# USB-C.net
KiCad netlist of a schematic drawn in Altium Designer
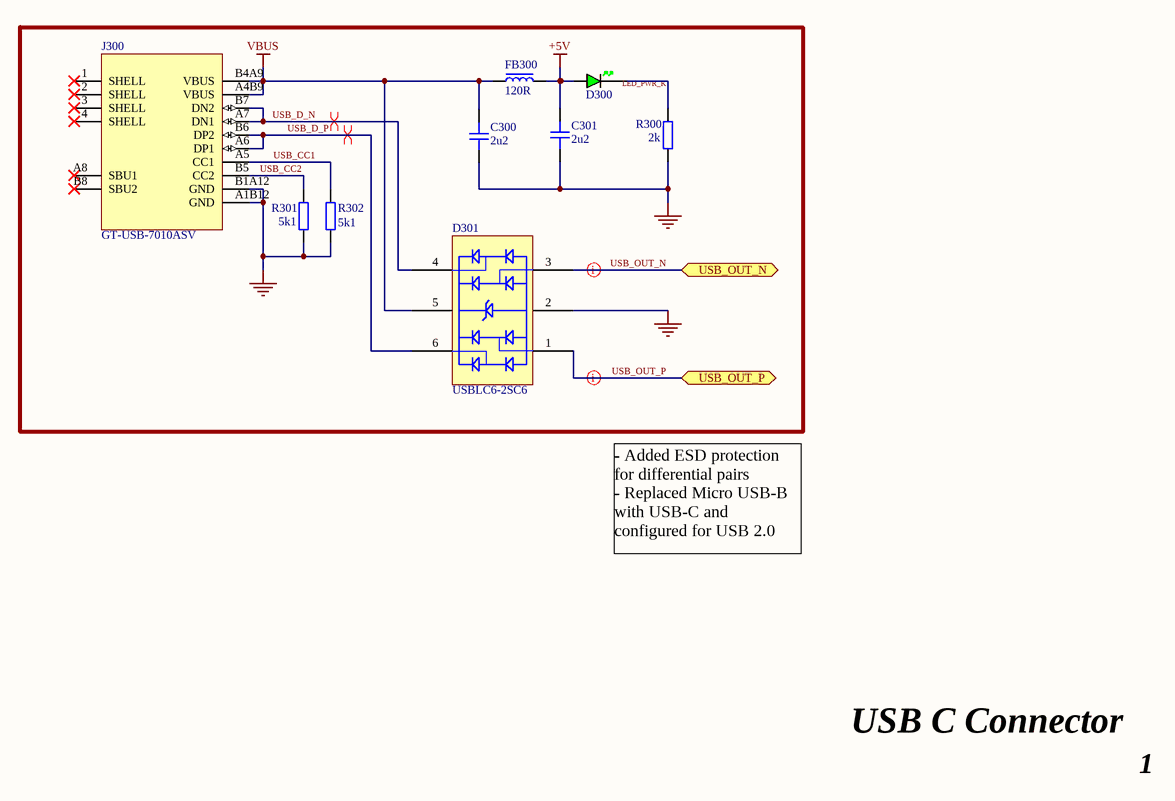
[diagram p0: USB-C.SchDoc]

(export (version "E")
  (design (tool "Eeschema 10.0.6"))
  (components
    (comp (ref "C300")
      (value "2u2")
      (footprint "CAP_0603")
      (description "Capacitor SMD 0603")
      (libsource (lib "Footprint-Lib-PhilsLab") (part "CAP_0603"))
    )
    (comp (ref "C301")
      (value "2u2")
      (footprint "CAP_0603")
      (description "Capacitor SMD 0603")
      (libsource (lib "Footprint-Lib-PhilsLab") (part "CAP_0603"))
    )
    (comp (ref "D300")
      (value "GREEN")
      (footprint "LED_0603_GREEN")
      (description "LED 0603 GREEN SMD")
      (libsource (lib "Footprint-Lib-PhilsLab") (part "LED_0603_GREEN"))
    )
    (comp (ref "D301")
      (value "USBLC6-2SC6")
      (footprint "USBLC6-2SC6")
      (description "5A 17V 6V Unidirectional 5.25V SOT-23-6 ESD and Surge Protection (TVS/ESD) ROHS")
      (fields (field (name "MANUFACTURER") "STMicroelectronics") (field (name "JLCPCB PART NUMBER") "C7519"))
      (libsource (lib "Sidharth's Schematic Library") (part "USBLC6-2SC6"))
    )
    (comp (ref "FB300")
      (value "120R")
      (footprint "FB_0603")
      (description "Ferrite Bead SMD 0603")
      (libsource (lib "Footprint-Lib-PhilsLab") (part "FB_0603"))
    )
    (comp (ref "J300")
      (value "GT-USB-7010ASV")
      (footprint "GT-USB-7010ASV")
      (fields (field (name "MANUFACTURER") "G-Switch") (field (name "JLCPCB PART #") "C2988369"))
      (libsource (lib "Sidharth's Schematic Library") (part "GT-USB-7010ASV"))
    )
    (comp (ref "R300")
      (value "2k")
      (footprint "RES_0603")
      (description "Resistor SMD 0603")
      (libsource (lib "Footprint-Lib-PhilsLab") (part "RES_0603"))
    )
    (comp (ref "R301")
      (value "5k1")
      (footprint "RES_0603")
      (description "Resistor SMD 0603")
      (libsource (lib "Footprint-Lib-PhilsLab") (part "RES_0603"))
    )
    (comp (ref "R302")
      (value "5k1")
      (footprint "RES_0603")
      (description "Resistor SMD 0603")
      (libsource (lib "Footprint-Lib-PhilsLab") (part "RES_0603"))
    )
  )
  (nets
    (net (code "1") (name "+5V") (class "Default")
      (node (ref "C301") (pin "2") (pinfunction "2_2") (pintype "passive"))
      (node (ref "D300") (pin "A") (pinfunction "A_A") (pintype "passive"))
      (node (ref "FB300") (pin "2") (pinfunction "2_2") (pintype "passive"))
    )
    (net (code "2") (name "/LED_PWR_K") (class "Default")
      (node (ref "D300") (pin "K") (pinfunction "K_K") (pintype "passive"))
      (node (ref "R300") (pin "2") (pinfunction "2_2") (pintype "passive"))
    )
    (net (code "3") (name "/USB_CC1") (class "Default")
      (node (ref "J300") (pin "A5") (pinfunction "CC1_A5") (pintype "passive"))
      (node (ref "R302") (pin "2") (pinfunction "2_2") (pintype "passive"))
    )
    (net (code "4") (name "/USB_CC2") (class "Default")
      (node (ref "J300") (pin "B5") (pinfunction "CC2_B5") (pintype "passive"))
      (node (ref "R301") (pin "2") (pinfunction "2_2") (pintype "passive"))
    )
    (net (code "5") (name "/USB_D_N") (class "Default")
      (node (ref "D301") (pin "4") (pintype "passive"))
      (node (ref "J300") (pin "A7") (pinfunction "DN1_A7") (pintype "bidirectional"))
      (node (ref "J300") (pin "B7") (pinfunction "DN2_B7") (pintype "bidirectional"))
    )
    (net (code "6") (name "/USB_D_P") (class "Default")
      (node (ref "D301") (pin "6") (pintype "passive"))
      (node (ref "J300") (pin "A6") (pinfunction "DP1_A6") (pintype "bidirectional"))
      (node (ref "J300") (pin "B6") (pinfunction "DP2_B6") (pintype "bidirectional"))
    )
    (net (code "7") (name "/USB_OUT_N") (class "Default") (node (ref "D301") (pin "3") (pintype "passive")))
    (net (code "8") (name "/USB_OUT_P") (class "Default") (node (ref "D301") (pin "1") (pintype "passive")))
    (net (code "9") (name "GND") (class "Default")
      (node (ref "C300") (pin "1") (pinfunction "1_1") (pintype "passive"))
      (node (ref "C301") (pin "1") (pinfunction "1_1") (pintype "passive"))
      (node (ref "D301") (pin "2") (pintype "passive"))
      (node (ref "J300") (pin "A1B12") (pinfunction "GND_A1B12") (pintype "passive"))
      (node (ref "J300") (pin "B1A12") (pinfunction "GND_B1A12") (pintype "passive"))
      (node (ref "R300") (pin "1") (pinfunction "1_1") (pintype "passive"))
      (node (ref "R301") (pin "1") (pinfunction "1_1") (pintype "passive"))
      (node (ref "R302") (pin "1") (pinfunction "1_1") (pintype "passive"))
    )
    (net (code "10") (name "VBUS") (class "Default")
      (node (ref "C300") (pin "2") (pinfunction "2_2") (pintype "passive"))
      (node (ref "D301") (pin "5") (pintype "passive"))
      (node (ref "FB300") (pin "1") (pinfunction "1_1") (pintype "passive"))
      (node (ref "J300") (pin "A4B9") (pinfunction "VBUS_A4B9") (pintype "passive"))
      (node (ref "J300") (pin "B4A9") (pinfunction "VBUS_B4A9") (pintype "passive"))
    )
    (net (code "11") (name "unconnected-(J300-SBU1-PadA8)") (class "Default")
      (node (ref "J300") (pin "A8") (pinfunction "SBU1_A8") (pintype "passive+no_connect"))
    )
    (net (code "12") (name "unconnected-(J300-SBU2-PadB8)") (class "Default")
      (node (ref "J300") (pin "B8") (pinfunction "SBU2_B8") (pintype "passive+no_connect"))
    )
    (net (code "13") (name "unconnected-(J300-SHELL-Pad1)") (class "Default")
      (node (ref "J300") (pin "1") (pinfunction "SHELL_1") (pintype "passive+no_connect"))
    )
    (net (code "14") (name "unconnected-(J300-SHELL-Pad2)") (class "Default")
      (node (ref "J300") (pin "2") (pinfunction "SHELL_2") (pintype "passive+no_connect"))
    )
    (net (code "15") (name "unconnected-(J300-SHELL-Pad3)") (class "Default")
      (node (ref "J300") (pin "3") (pinfunction "SHELL_3") (pintype "passive+no_connect"))
    )
    (net (code "16") (name "unconnected-(J300-SHELL-Pad4)") (class "Default")
      (node (ref "J300") (pin "4") (pinfunction "SHELL_4") (pintype "passive+no_connect"))
    )
  )
)
